# Sheet1.net
KiCad netlist of a schematic drawn in Altium Designer
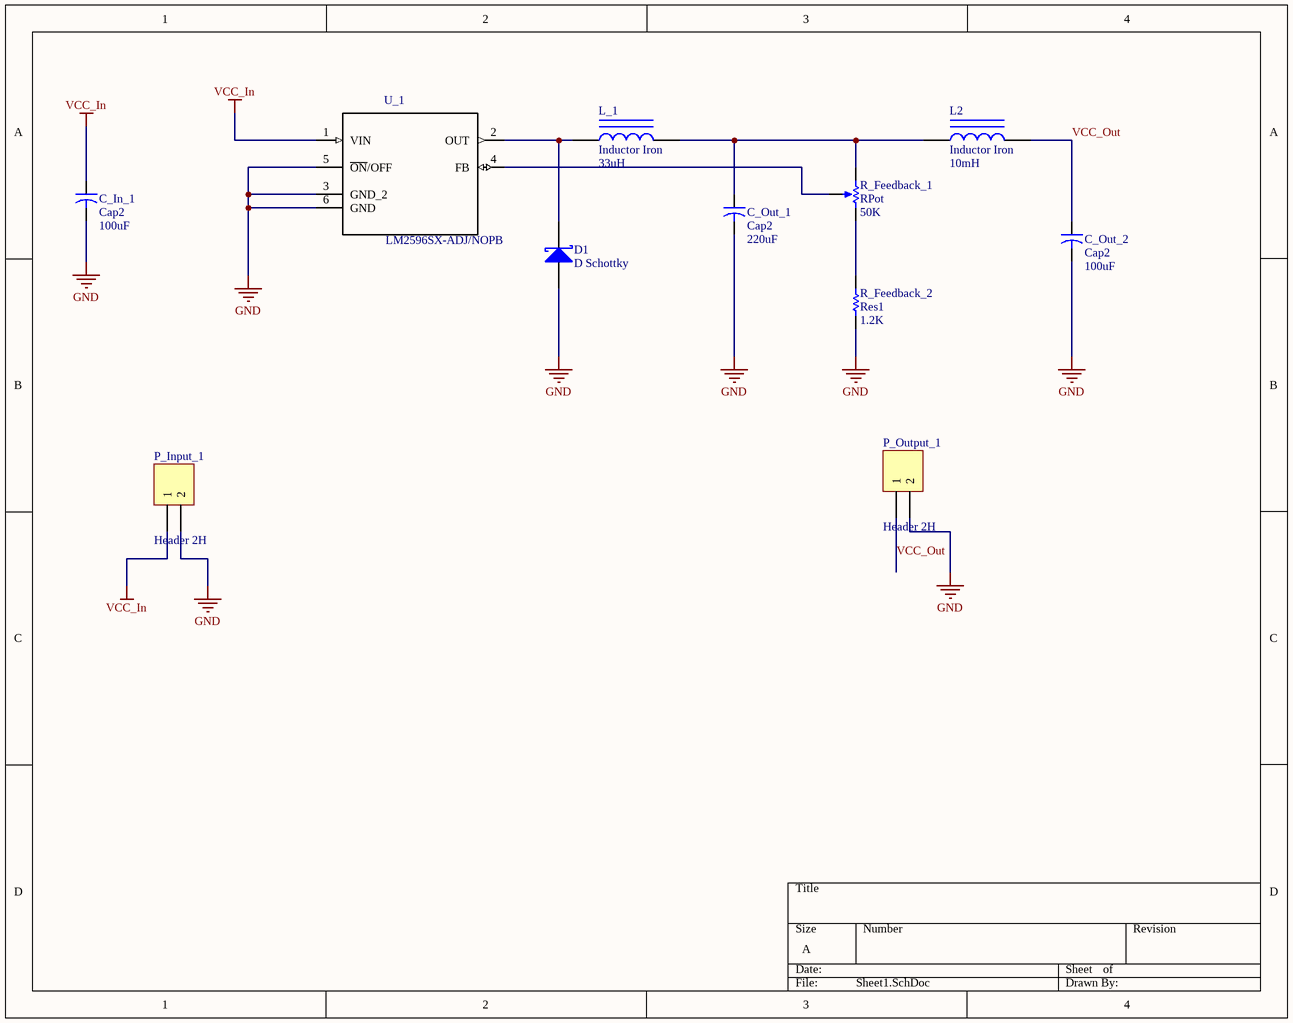
[diagram p0: Sheet1.SchDoc]

(export (version "E")
  (design (tool "Eeschema 10.0.6"))
  (components
    (comp (ref "C_In_1")
      (value "Cap2")
      (footprint "CAPR5-4X5")
      (description "Capacitor")
      (fields (field (name "ALTIUM_VALUE") "100uF") (field (name "PUBLISHER") "Altium Limited"))
      (libsource (lib "Miscellaneous Devices") (part "Cap2"))
    )
    (comp (ref "C_Out_1")
      (value "Cap2")
      (footprint "CAPR5-4X5")
      (description "Capacitor")
      (fields (field (name "ALTIUM_VALUE") "220uF") (field (name "PUBLISHER") "Altium Limited"))
      (libsource (lib "Miscellaneous Devices") (part "Cap2"))
    )
    (comp (ref "C_Out_2")
      (value "Cap2")
      (footprint "CAPR5-4X5")
      (description "Capacitor")
      (fields (field (name "ALTIUM_VALUE") "100uF") (field (name "PUBLISHER") "Altium Limited"))
      (libsource (lib "Miscellaneous Devices") (part "Cap2"))
    )
    (comp (ref "D1")
      (value "D Schottky")
      (footprint "SMB")
      (description "Schottky Diode")
      (fields (field (name "PUBLISHER") "Altium Limited"))
      (libsource (lib "Miscellaneous Devices") (part "D Schottky"))
    )
    (comp (ref "L2")
      (value "Inductor Iron")
      (footprint "AXIAL-0.9")
      (description "Magnetic-Core Inductor")
      (fields (field (name "ALTIUM_VALUE") "10mH") (field (name "PUBLISHER") "Altium Limited"))
      (libsource (lib "Miscellaneous Devices") (part "Inductor Iron"))
    )
    (comp (ref "L_1")
      (value "Inductor Iron")
      (footprint "AXIAL-0.9")
      (description "Magnetic-Core Inductor")
      (fields (field (name "ALTIUM_VALUE") "33uH") (field (name "PUBLISHER") "Altium Limited"))
      (libsource (lib "Miscellaneous Devices") (part "Inductor Iron"))
    )
    (comp (ref "P_Input_1")
      (value "Header 2H")
      (footprint "HDR1X2H")
      (description "Header, 2-Pin, Right Angle")
      (fields (field (name "PUBLISHER") "Altium Limited"))
      (libsource (lib "Miscellaneous Connectors") (part "Header 2H"))
    )
    (comp (ref "P_Output_1")
      (value "Header 2H")
      (footprint "HDR1X2H")
      (description "Header, 2-Pin, Right Angle")
      (fields (field (name "PUBLISHER") "Altium Limited"))
      (libsource (lib "Miscellaneous Connectors") (part "Header 2H"))
    )
    (comp (ref "R_Feedback_1")
      (value "RPot")
      (footprint "VR5")
      (description "Potentiometer")
      (fields (field (name "ALTIUM_VALUE") "50K") (field (name "PUBLISHER") "Altium Limited"))
      (libsource (lib "Miscellaneous Devices") (part "RPot"))
    )
    (comp (ref "R_Feedback_2")
      (value "Res1")
      (footprint "AXIAL-0.3")
      (description "Resistor")
      (fields (field (name "ALTIUM_VALUE") "1.2K") (field (name "PUBLISHER") "Altium Limited"))
      (libsource (lib "Miscellaneous Devices") (part "Res1"))
    )
    (comp (ref "U_1")
      (value "LM2596SX-ADJ/NOPB")
      (footprint "TO170P1435X465-6N")
      (description "SIMPLE SWITCHER® 4.5V to 40V, 3A Low Component Count Step-Down Regulator 5-DDPAK/TO-263 -40 to 125")
      (fields (field (name "MF") "Texas Instruments"))
      (libsource (lib "LM2596SX-ADJ_NOPB") (part "LM2596SX-ADJ/NOPB"))
    )
  )
  (nets
    (net (code "1") (name "/VCC_Out") (class "Default")
      (node (ref "C_Out_2") (pin "1") (pinfunction "1_1") (pintype "passive"))
      (node (ref "L2") (pin "2") (pinfunction "2_2") (pintype "passive"))
      (node (ref "P_Output_1") (pin "1") (pinfunction "1_1") (pintype "passive"))
    )
    (net (code "2") (name "GND") (class "Default")
      (node (ref "C_In_1") (pin "2") (pinfunction "2_2") (pintype "passive"))
      (node (ref "C_Out_1") (pin "2") (pinfunction "2_2") (pintype "passive"))
      (node (ref "C_Out_2") (pin "2") (pinfunction "2_2") (pintype "passive"))
      (node (ref "D1") (pin "1") (pinfunction "A_1") (pintype "passive"))
      (node (ref "P_Input_1") (pin "2") (pinfunction "2_2") (pintype "passive"))
      (node (ref "P_Output_1") (pin "2") (pinfunction "2_2") (pintype "passive"))
      (node (ref "R_Feedback_2") (pin "1") (pinfunction "1_1") (pintype "passive"))
      (node (ref "U_1") (pin "3") (pinfunction "GND_2_3") (pintype "passive"))
      (node (ref "U_1") (pin "5") (pinfunction "~{ON}/OFF_5") (pintype "passive"))
      (node (ref "U_1") (pin "6") (pinfunction "GND_6") (pintype "passive"))
    )
    (net (code "3") (name "Net-(D1-K)") (class "Default")
      (node (ref "D1") (pin "2") (pinfunction "K_2") (pintype "passive"))
      (node (ref "L_1") (pin "1") (pinfunction "1_1") (pintype "passive"))
      (node (ref "U_1") (pin "2") (pinfunction "OUT_2") (pintype "output"))
    )
    (net (code "4") (name "Net-(R_Feedback_1-BOT)") (class "Default")
      (node (ref "R_Feedback_1") (pin "2") (pinfunction "BOT_2") (pintype "passive"))
      (node (ref "R_Feedback_2") (pin "2") (pinfunction "2_2") (pintype "passive"))
    )
    (net (code "5") (name "Net-(R_Feedback_1-TAP)") (class "Default")
      (node (ref "R_Feedback_1") (pin "3") (pinfunction "TAP_3") (pintype "passive"))
      (node (ref "U_1") (pin "4") (pinfunction "FB_4") (pintype "bidirectional"))
    )
    (net (code "6") (name "Net-(R_Feedback_1-TOP)") (class "Default")
      (node (ref "C_Out_1") (pin "1") (pinfunction "1_1") (pintype "passive"))
      (node (ref "L2") (pin "1") (pinfunction "1_1") (pintype "passive"))
      (node (ref "L_1") (pin "2") (pinfunction "2_2") (pintype "passive"))
      (node (ref "R_Feedback_1") (pin "1") (pinfunction "TOP_1") (pintype "passive"))
    )
    (net (code "7") (name "VCC_In") (class "Default")
      (node (ref "C_In_1") (pin "1") (pinfunction "1_1") (pintype "passive"))
      (node (ref "P_Input_1") (pin "1") (pinfunction "1_1") (pintype "passive"))
      (node (ref "U_1") (pin "1") (pinfunction "VIN_1") (pintype "input"))
    )
  )
)
